# supply.net
KiCad netlist of a schematic drawn in EAGLE
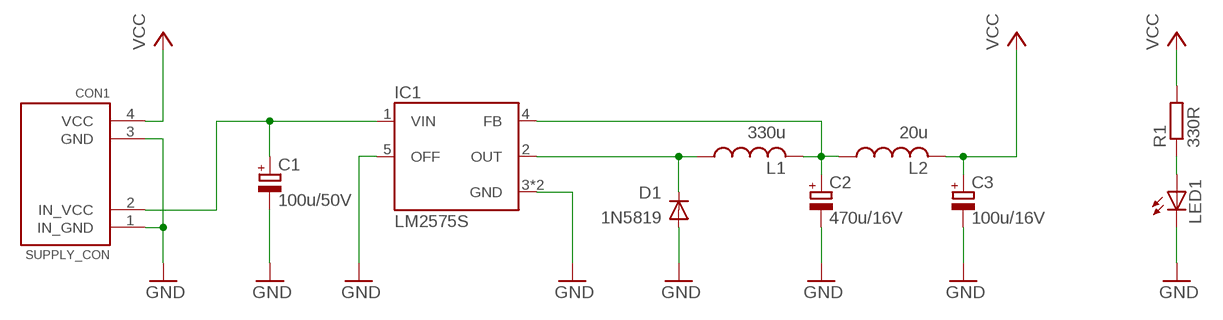
[diagram p0: schematic, sheet 1]

(export (version "E")
  (design (tool "Eeschema 10.0.6"))
  (components
    (comp (ref "C1")
      (value "100u/50V")
      (footprint "eagle-import:E3,5-8")
      (libsource (lib "eagle-import") (part "CPOL-EUE3.5-8"))
    )
    (comp (ref "C2")
      (value "470u/16V")
      (footprint "eagle-import:E5-10,5")
      (libsource (lib "eagle-import") (part "CPOL-EUE5-10.5"))
    )
    (comp (ref "C3")
      (value "100u/16V")
      (footprint "eagle-import:E2,5-6")
      (libsource (lib "eagle-import") (part "CPOL-EUE2.5-6"))
    )
    (comp (ref "CON1")
      (value "SUPPLY_CON")
      (footprint "eagle-import:SUPPLY_CON")
      (libsource (lib "eagle-import") (part "SUPPLY_CON"))
    )
    (comp (ref "D1")
      (value "1N5819")
      (footprint "eagle-import:DO41-10")
      (libsource (lib "eagle-import") (part "1N4004"))
    )
    (comp (ref "IC1")
      (value "LM2575S")
      (footprint "eagle-import:TO263-5")
      (libsource (lib "eagle-import") (part "LM2575S"))
    )
    (comp (ref "L1")
      (value "330u")
      (footprint "eagle-import:COIL")
      (libsource (lib "eagle-import") (part "COIL"))
    )
    (comp (ref "L2")
      (value "20u")
      (footprint "eagle-import:COIL")
      (libsource (lib "eagle-import") (part "COIL"))
    )
    (comp (ref "LED1")
      (value "LEDSML1206")
      (footprint "eagle-import:SML1206")
      (libsource (lib "eagle-import") (part "LEDSML1206"))
    )
    (comp (ref "R1")
      (value "330R")
      (footprint "eagle-import:R0603")
      (libsource (lib "eagle-import") (part "R-EU_R0603"))
    )
  )
  (nets
    (net (code "1") (name "GND") (class "Default")
      (node (ref "C1") (pin "-") (pinfunction "-_-") (pintype "passive"))
      (node (ref "C2") (pin "-") (pinfunction "-_-") (pintype "passive"))
      (node (ref "C3") (pin "-") (pinfunction "-_-") (pintype "passive"))
      (node (ref "CON1") (pin "1") (pinfunction "IN_GND_1") (pintype "bidirectional"))
      (node (ref "CON1") (pin "3") (pinfunction "GND_3") (pintype "bidirectional"))
      (node (ref "D1") (pin "A") (pinfunction "A_A") (pintype "passive"))
      (node (ref "IC1") (pin "3") (pinfunction "GND_3") (pintype "power_in"))
      (node (ref "IC1") (pin "5") (pinfunction "OFF_5") (pintype "input"))
      (node (ref "IC1") (pin "6") (pinfunction "GND_6") (pintype "power_in"))
      (node (ref "LED1") (pin "C") (pinfunction "C_C") (pintype "passive"))
    )
    (net (code "2") (name "Net-(CON1-IN_VCC)") (class "Default")
      (node (ref "C1") (pin "+") (pinfunction "+_+") (pintype "passive"))
      (node (ref "CON1") (pin "2") (pinfunction "IN_VCC_2") (pintype "bidirectional"))
      (node (ref "IC1") (pin "1") (pinfunction "VIN_1") (pintype "power_in"))
    )
    (net (code "3") (name "Net-(IC1-FB)") (class "Default")
      (node (ref "C2") (pin "+") (pinfunction "+_+") (pintype "passive"))
      (node (ref "IC1") (pin "4") (pinfunction "FB_4") (pintype "input"))
      (node (ref "L1") (pin "P$2") (pinfunction "P$2_P$2") (pintype "passive"))
      (node (ref "L2") (pin "P$1") (pinfunction "P$1_P$1") (pintype "passive"))
    )
    (net (code "4") (name "Net-(IC1-OUT)") (class "Default")
      (node (ref "D1") (pin "C") (pinfunction "C_C") (pintype "passive"))
      (node (ref "IC1") (pin "2") (pinfunction "OUT_2") (pintype "output"))
      (node (ref "L1") (pin "P$1") (pinfunction "P$1_P$1") (pintype "passive"))
    )
    (net (code "5") (name "Net-(LED1-PadA)") (class "Default")
      (node (ref "LED1") (pin "A") (pinfunction "A_A") (pintype "passive"))
      (node (ref "R1") (pin "1") (pinfunction "1_1") (pintype "passive"))
    )
    (net (code "6") (name "VCC") (class "Default")
      (node (ref "C3") (pin "+") (pinfunction "+_+") (pintype "passive"))
      (node (ref "CON1") (pin "4") (pinfunction "VCC_4") (pintype "bidirectional"))
      (node (ref "L2") (pin "P$2") (pinfunction "P$2_P$2") (pintype "passive"))
      (node (ref "R1") (pin "2") (pinfunction "2_2") (pintype "passive"))
    )
  )
)
